# power-new.net
KiCad netlist of a schematic drawn in EAGLE
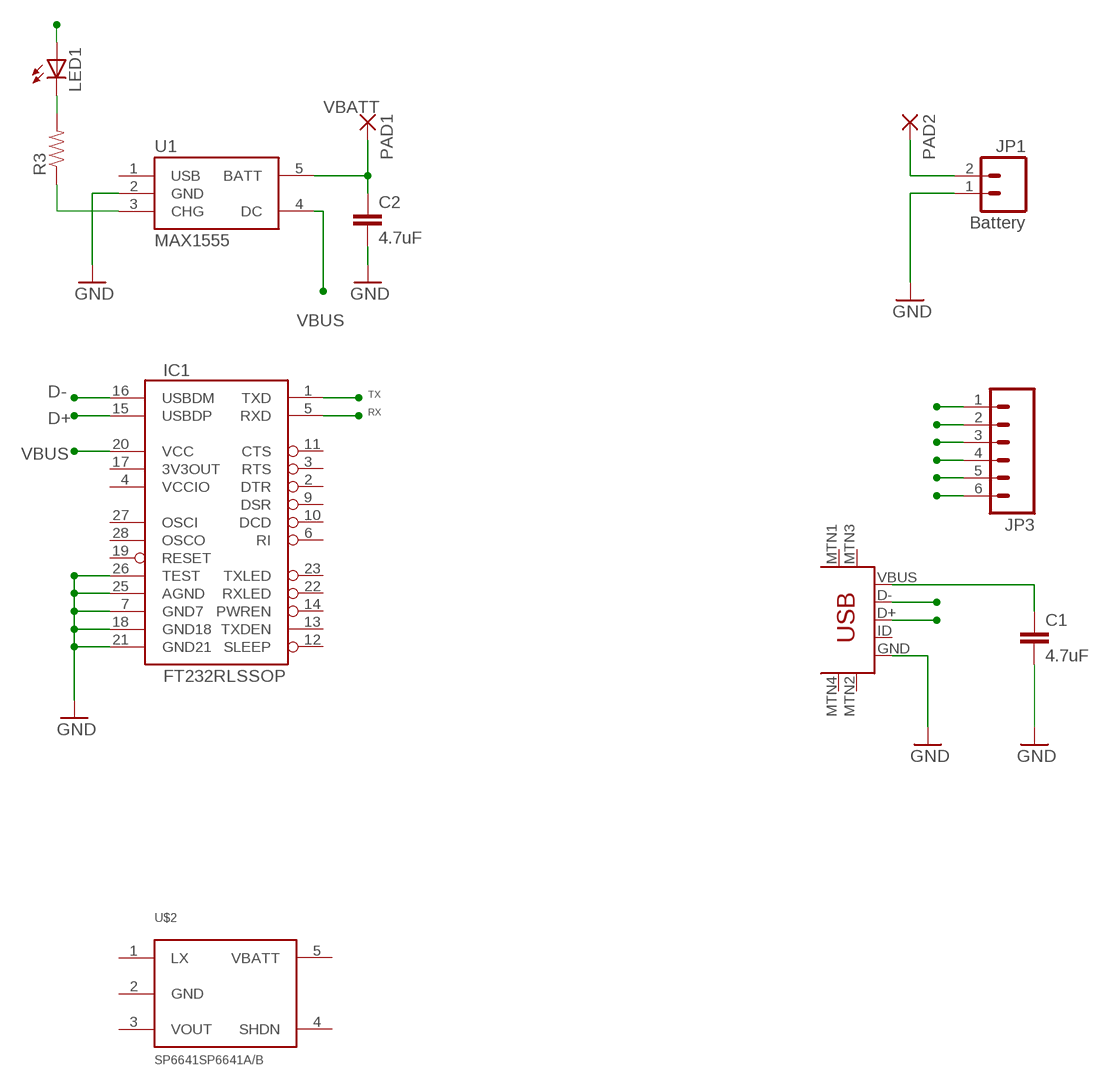
[diagram p0: schematic, sheet 1]

(export (version "E")
  (design (tool "Eeschema 10.0.6"))
  (components
    (comp (ref "C1")
      (value "4.7uF")
      (footprint "eagle-import:1206")
      (libsource (lib "eagle-import") (part "CAP1206"))
    )
    (comp (ref "C2")
      (value "4.7uF")
      (footprint "eagle-import:1206")
      (libsource (lib "eagle-import") (part "CAP1206"))
    )
    (comp (ref "IC1")
      (value "FT232RLSSOP")
      (footprint "eagle-import:SSOP28DB")
      (libsource (lib "eagle-import") (part "FT232RLSSOP"))
    )
    (comp (ref "JP1")
      (value "Battery")
      (footprint "eagle-import:JST-2-SMD")
      (libsource (lib "eagle-import") (part "M02-JST-2MM-SMT"))
    )
    (comp (ref "JP3")
      (value "M061X06-SMD_EDGE_FEMALE")
      (footprint "eagle-import:1X06-SMD_EDGE")
      (libsource (lib "eagle-import") (part "M061X06-SMD_EDGE_FEMALE"))
    )
    (comp (ref "LED1")
      (value "LED0603")
      (footprint "eagle-import:LED-0603")
      (libsource (lib "eagle-import") (part "LED0603"))
    )
    (comp (ref "PAD1")
      (value "WIREPAD2,54/1,0")
      (footprint "eagle-import:2,54_1,0")
      (libsource (lib "eagle-import") (part "WIREPAD2,54/1,0"))
    )
    (comp (ref "PAD2")
      (value "WIREPAD2,54/1,0")
      (footprint "eagle-import:2,54_1,0")
      (libsource (lib "eagle-import") (part "WIREPAD2,54/1,0"))
    )
    (comp (ref "R3")
      (value "RESISTOR0603-RES")
      (footprint "eagle-import:0603-RES")
      (libsource (lib "eagle-import") (part "RESISTOR0603-RES"))
    )
    (comp (ref "U$1")
      (value "USB-MINIB-5PIN")
      (footprint "eagle-import:USB-MINIB")
      (libsource (lib "eagle-import") (part "USB-MINIB-5PIN"))
    )
    (comp (ref "U$2")
      (value "SP6641SP6641A/B")
      (footprint "eagle-import:SOT23-5")
      (libsource (lib "eagle-import") (part "SP6641SP6641A/B"))
    )
    (comp (ref "U1")
      (value "MAX1555")
      (footprint "eagle-import:SOT23-5")
      (libsource (lib "eagle-import") (part "MAX1555"))
    )
  )
  (nets
    (net (code "1") (name "/D+") (class "Default")
      (node (ref "IC1") (pin "15") (pinfunction "USBDP_15") (pintype "bidirectional"))
      (node (ref "U$1") (pin "D+") (pinfunction "D+_D+") (pintype "bidirectional"))
    )
    (net (code "2") (name "/D-") (class "Default")
      (node (ref "IC1") (pin "16") (pinfunction "USBDM_16") (pintype "bidirectional"))
      (node (ref "U$1") (pin "D-") (pinfunction "D-_D-") (pintype "bidirectional"))
    )
    (net (code "3") (name "/RX") (class "Default")
      (node (ref "IC1") (pin "5") (pinfunction "RXD_5") (pintype "input"))
      (node (ref "JP3") (pin "1") (pinfunction "1_1") (pintype "passive"))
    )
    (net (code "4") (name "/TX") (class "Default")
      (node (ref "IC1") (pin "1") (pinfunction "TXD_1") (pintype "output"))
      (node (ref "JP3") (pin "2") (pinfunction "2_2") (pintype "passive"))
    )
    (net (code "5") (name "/VBATT") (class "Default")
      (node (ref "C2") (pin "1") (pinfunction "1_1") (pintype "passive"))
      (node (ref "JP3") (pin "4") (pinfunction "4_4") (pintype "passive"))
      (node (ref "PAD1") (pin "1") (pinfunction "P_1") (pintype "passive"))
      (node (ref "U1") (pin "5") (pinfunction "BATT_5") (pintype "bidirectional"))
    )
    (net (code "6") (name "/VBUS") (class "Default")
      (node (ref "C1") (pin "1") (pinfunction "1_1") (pintype "passive"))
      (node (ref "IC1") (pin "20") (pinfunction "VCC_20") (pintype "power_in"))
      (node (ref "JP3") (pin "3") (pinfunction "3_3") (pintype "passive"))
      (node (ref "LED1") (pin "A") (pinfunction "A_A") (pintype "passive"))
      (node (ref "U$1") (pin "VBUS") (pinfunction "VBUS_VBUS") (pintype "bidirectional"))
      (node (ref "U1") (pin "4") (pinfunction "DC_4") (pintype "bidirectional"))
    )
    (net (code "7") (name "/VCCIO") (class "Default")
      (node (ref "IC1") (pin "4") (pinfunction "VCCIO_4") (pintype "power_in"))
    )
    (net (code "8") (name "GND") (class "Default")
      (node (ref "C1") (pin "2") (pinfunction "2_2") (pintype "passive"))
      (node (ref "C2") (pin "2") (pinfunction "2_2") (pintype "passive"))
      (node (ref "IC1") (pin "18") (pinfunction "GND18_18") (pintype "power_in"))
      (node (ref "IC1") (pin "21") (pinfunction "GND21_21") (pintype "power_in"))
      (node (ref "IC1") (pin "25") (pinfunction "AGND_25") (pintype "power_in"))
      (node (ref "IC1") (pin "26") (pinfunction "TEST_26") (pintype "input"))
      (node (ref "IC1") (pin "7") (pinfunction "GND7_7") (pintype "power_in"))
      (node (ref "JP1") (pin "1") (pinfunction "1_1") (pintype "passive"))
      (node (ref "JP3") (pin "6") (pinfunction "6_6") (pintype "passive"))
      (node (ref "U$1") (pin "GND") (pinfunction "GND_GND") (pintype "bidirectional"))
      (node (ref "U1") (pin "2") (pinfunction "GND_2") (pintype "bidirectional"))
    )
    (net (code "9") (name "Net-(LED1-PadC)") (class "Default")
      (node (ref "LED1") (pin "C") (pinfunction "C_C") (pintype "passive"))
      (node (ref "R3") (pin "2") (pinfunction "2_2") (pintype "passive"))
    )
    (net (code "10") (name "Net-(PAD2-P)") (class "Default")
      (node (ref "JP1") (pin "2") (pinfunction "2_2") (pintype "passive"))
      (node (ref "PAD2") (pin "1") (pinfunction "P_1") (pintype "passive"))
    )
    (net (code "11") (name "Net-(U1-CHG)") (class "Default")
      (node (ref "R3") (pin "1") (pinfunction "1_1") (pintype "passive"))
      (node (ref "U1") (pin "3") (pinfunction "CHG_3") (pintype "bidirectional"))
    )
    (net (code "12") (name "unconnected-(IC1-3V3OUT-Pad17)") (class "Default")
      (node (ref "IC1") (pin "17") (pinfunction "3V3OUT_17") (pintype "output"))
    )
    (net (code "13") (name "unconnected-(IC1-CTS-Pad11)") (class "Default")
      (node (ref "IC1") (pin "11") (pinfunction "CTS_11") (pintype "input"))
    )
    (net (code "14") (name "unconnected-(IC1-DCD-Pad10)") (class "Default")
      (node (ref "IC1") (pin "10") (pinfunction "DCD_10") (pintype "input"))
    )
    (net (code "15") (name "unconnected-(IC1-DSR-Pad9)") (class "Default")
      (node (ref "IC1") (pin "9") (pinfunction "DSR_9") (pintype "input"))
    )
    (net (code "16") (name "unconnected-(IC1-DTR-Pad2)") (class "Default")
      (node (ref "IC1") (pin "2") (pinfunction "DTR_2") (pintype "output"))
    )
    (net (code "17") (name "unconnected-(IC1-OSCI-Pad27)") (class "Default")
      (node (ref "IC1") (pin "27") (pinfunction "OSCI_27") (pintype "input"))
    )
    (net (code "18") (name "unconnected-(IC1-OSCO-Pad28)") (class "Default")
      (node (ref "IC1") (pin "28") (pinfunction "OSCO_28") (pintype "output"))
    )
    (net (code "19") (name "unconnected-(IC1-PWREN-Pad14)") (class "Default")
      (node (ref "IC1") (pin "14") (pinfunction "PWREN_14") (pintype "input"))
    )
    (net (code "20") (name "unconnected-(IC1-RESET-Pad19)") (class "Default")
      (node (ref "IC1") (pin "19") (pinfunction "RESET_19") (pintype "input"))
    )
    (net (code "21") (name "unconnected-(IC1-RI-Pad6)") (class "Default")
      (node (ref "IC1") (pin "6") (pinfunction "RI_6") (pintype "input"))
    )
    (net (code "22") (name "unconnected-(IC1-RTS-Pad3)") (class "Default")
      (node (ref "IC1") (pin "3") (pinfunction "RTS_3") (pintype "output"))
    )
    (net (code "23") (name "unconnected-(IC1-RXLED-Pad22)") (class "Default")
      (node (ref "IC1") (pin "22") (pinfunction "RXLED_22") (pintype "input"))
    )
    (net (code "24") (name "unconnected-(IC1-SLEEP-Pad12)") (class "Default")
      (node (ref "IC1") (pin "12") (pinfunction "SLEEP_12") (pintype "input"))
    )
    (net (code "25") (name "unconnected-(IC1-TXDEN-Pad13)") (class "Default")
      (node (ref "IC1") (pin "13") (pinfunction "TXDEN_13") (pintype "input"))
    )
    (net (code "26") (name "unconnected-(IC1-TXLED-Pad23)") (class "Default")
      (node (ref "IC1") (pin "23") (pinfunction "TXLED_23") (pintype "input"))
    )
    (net (code "27") (name "unconnected-(JP3-Pad5)") (class "Default")
      (node (ref "JP3") (pin "5") (pinfunction "5_5") (pintype "passive"))
    )
    (net (code "28") (name "unconnected-(U$1-MTN1-PadMTN3)") (class "Default")
      (node (ref "U$1") (pin "MTN3") (pinfunction "MTN1_MTN3") (pintype "bidirectional"))
    )
    (net (code "29") (name "unconnected-(U$1-MTN2-PadMTN1)") (class "Default")
      (node (ref "U$1") (pin "MTN1") (pinfunction "MTN2_MTN1") (pintype "bidirectional"))
    )
    (net (code "30") (name "unconnected-(U$1-MTN3-PadMTN2)") (class "Default")
      (node (ref "U$1") (pin "MTN2") (pinfunction "MTN3_MTN2") (pintype "bidirectional"))
    )
    (net (code "31") (name "unconnected-(U$1-PadID)") (class "Default")
      (node (ref "U$1") (pin "ID") (pinfunction "ID_ID") (pintype "bidirectional"))
    )
    (net (code "32") (name "unconnected-(U$1-PadMTN4)") (class "Default")
      (node (ref "U$1") (pin "MTN4") (pinfunction "MTN4_MTN4") (pintype "bidirectional"))
    )
    (net (code "33") (name "unconnected-(U$2-GND-Pad2)") (class "Default")
      (node (ref "U$2") (pin "2") (pinfunction "GND_2") (pintype "bidirectional"))
    )
    (net (code "34") (name "unconnected-(U$2-LX-Pad1)") (class "Default")
      (node (ref "U$2") (pin "1") (pinfunction "LX_1") (pintype "bidirectional"))
    )
    (net (code "35") (name "unconnected-(U$2-SHDN-Pad4)") (class "Default")
      (node (ref "U$2") (pin "4") (pinfunction "SHDN_4") (pintype "bidirectional"))
    )
    (net (code "36") (name "unconnected-(U$2-VBATT-Pad5)") (class "Default")
      (node (ref "U$2") (pin "5") (pinfunction "VBATT_5") (pintype "bidirectional"))
    )
    (net (code "37") (name "unconnected-(U$2-VOUT-Pad3)") (class "Default")
      (node (ref "U$2") (pin "3") (pinfunction "VOUT_3") (pintype "bidirectional"))
    )
    (net (code "38") (name "unconnected-(U1-USB-Pad1)") (class "Default")
      (node (ref "U1") (pin "1") (pinfunction "USB_1") (pintype "bidirectional"))
    )
  )
)
